# RELAYS.net
KiCad netlist of a schematic drawn in Altium Designer
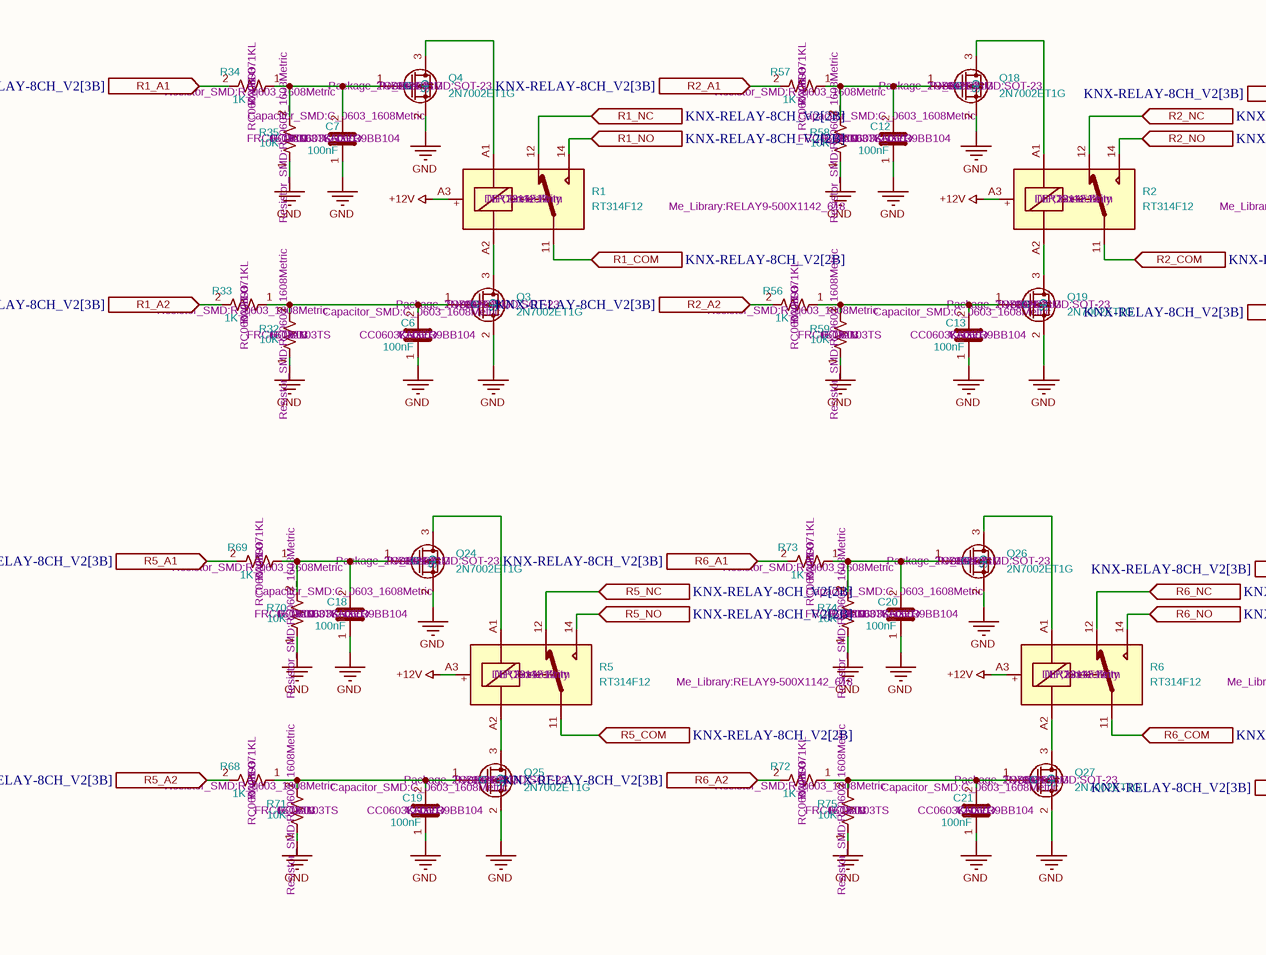
[diagram p0: RELAYS.SchDoc, left]
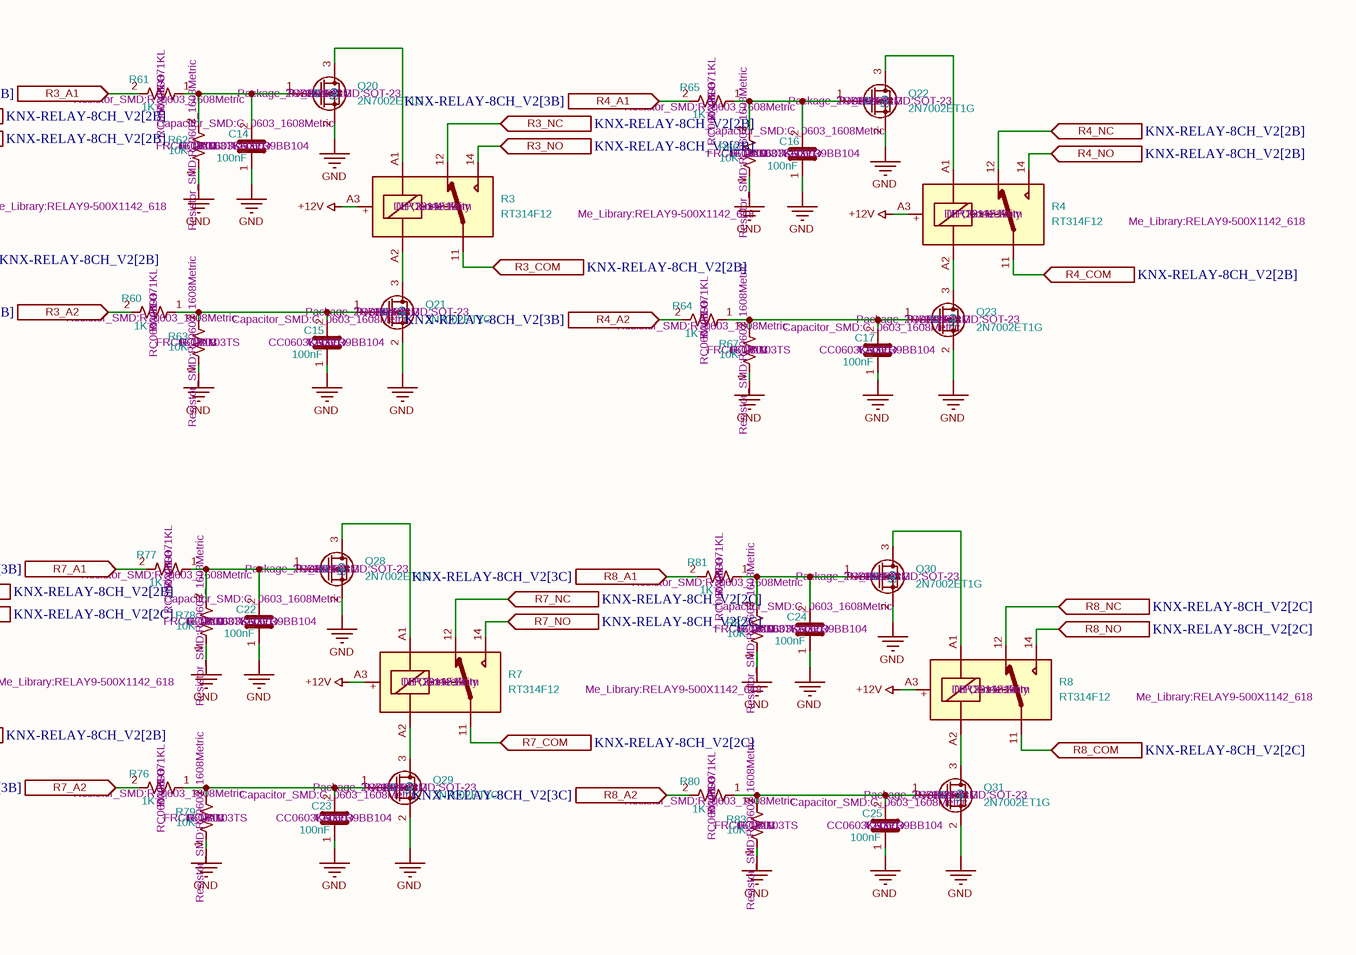
[diagram p1: RELAYS.SchDoc, right]

(export (version "E")
  (design (tool "Eeschema 10.0.6"))
  (components
    (comp (ref "C6")
      (value "100nF")
      (footprint "Capacitor_SMD:C_0603_1608Metric")
      (fields
        (field (name "MANUFACTURER PART NUMBER") "CC0603KRX7R9BB104")
        (field (name "MANUFACTURER") "YAGEO")
        (field (name "PACKAGE") "C_0603")
      )
      (libsource (lib "*") (part "C_3"))
    )
    (comp (ref "C7")
      (value "100nF")
      (footprint "Capacitor_SMD:C_0603_1608Metric")
      (fields
        (field (name "MANUFACTURER PART NUMBER") "CC0603KRX7R9BB104")
        (field (name "MANUFACTURER") "YAGEO")
        (field (name "PACKAGE") "C_0603")
      )
      (libsource (lib "*") (part "C_3"))
    )
    (comp (ref "C12")
      (value "100nF")
      (footprint "Capacitor_SMD:C_0603_1608Metric")
      (fields
        (field (name "MANUFACTURER PART NUMBER") "CC0603KRX7R9BB104")
        (field (name "MANUFACTURER") "YAGEO")
        (field (name "PACKAGE") "C_0603")
      )
      (libsource (lib "*") (part "C_3"))
    )
    (comp (ref "C13")
      (value "100nF")
      (footprint "Capacitor_SMD:C_0603_1608Metric")
      (fields
        (field (name "MANUFACTURER PART NUMBER") "CC0603KRX7R9BB104")
        (field (name "MANUFACTURER") "YAGEO")
        (field (name "PACKAGE") "C_0603")
      )
      (libsource (lib "*") (part "C_3"))
    )
    (comp (ref "C14")
      (value "100nF")
      (footprint "Capacitor_SMD:C_0603_1608Metric")
      (fields
        (field (name "MANUFACTURER PART NUMBER") "CC0603KRX7R9BB104")
        (field (name "MANUFACTURER") "YAGEO")
        (field (name "PACKAGE") "C_0603")
      )
      (libsource (lib "*") (part "C_3"))
    )
    (comp (ref "C15")
      (value "100nF")
      (footprint "Capacitor_SMD:C_0603_1608Metric")
      (fields
        (field (name "MANUFACTURER PART NUMBER") "CC0603KRX7R9BB104")
        (field (name "MANUFACTURER") "YAGEO")
        (field (name "PACKAGE") "C_0603")
      )
      (libsource (lib "*") (part "C_3"))
    )
    (comp (ref "C16")
      (value "100nF")
      (footprint "Capacitor_SMD:C_0603_1608Metric")
      (fields
        (field (name "MANUFACTURER PART NUMBER") "CC0603KRX7R9BB104")
        (field (name "MANUFACTURER") "YAGEO")
        (field (name "PACKAGE") "C_0603")
      )
      (libsource (lib "*") (part "C_3"))
    )
    (comp (ref "C17")
      (value "100nF")
      (footprint "Capacitor_SMD:C_0603_1608Metric")
      (fields
        (field (name "MANUFACTURER PART NUMBER") "CC0603KRX7R9BB104")
        (field (name "MANUFACTURER") "YAGEO")
        (field (name "PACKAGE") "C_0603")
      )
      (libsource (lib "*") (part "C_3"))
    )
    (comp (ref "C18")
      (value "100nF")
      (footprint "Capacitor_SMD:C_0603_1608Metric")
      (fields
        (field (name "MANUFACTURER PART NUMBER") "CC0603KRX7R9BB104")
        (field (name "MANUFACTURER") "YAGEO")
        (field (name "PACKAGE") "C_0603")
      )
      (libsource (lib "*") (part "C_3"))
    )
    (comp (ref "C19")
      (value "100nF")
      (footprint "Capacitor_SMD:C_0603_1608Metric")
      (fields
        (field (name "MANUFACTURER PART NUMBER") "CC0603KRX7R9BB104")
        (field (name "MANUFACTURER") "YAGEO")
        (field (name "PACKAGE") "C_0603")
      )
      (libsource (lib "*") (part "C_3"))
    )
    (comp (ref "C20")
      (value "100nF")
      (footprint "Capacitor_SMD:C_0603_1608Metric")
      (fields
        (field (name "MANUFACTURER PART NUMBER") "CC0603KRX7R9BB104")
        (field (name "MANUFACTURER") "YAGEO")
        (field (name "PACKAGE") "C_0603")
      )
      (libsource (lib "*") (part "C_3"))
    )
    (comp (ref "C21")
      (value "100nF")
      (footprint "Capacitor_SMD:C_0603_1608Metric")
      (fields
        (field (name "MANUFACTURER PART NUMBER") "CC0603KRX7R9BB104")
        (field (name "MANUFACTURER") "YAGEO")
        (field (name "PACKAGE") "C_0603")
      )
      (libsource (lib "*") (part "C_3"))
    )
    (comp (ref "C22")
      (value "100nF")
      (footprint "Capacitor_SMD:C_0603_1608Metric")
      (fields
        (field (name "MANUFACTURER PART NUMBER") "CC0603KRX7R9BB104")
        (field (name "MANUFACTURER") "YAGEO")
        (field (name "PACKAGE") "C_0603")
      )
      (libsource (lib "*") (part "C_3"))
    )
    (comp (ref "C23")
      (value "100nF")
      (footprint "Capacitor_SMD:C_0603_1608Metric")
      (fields
        (field (name "MANUFACTURER PART NUMBER") "CC0603KRX7R9BB104")
        (field (name "MANUFACTURER") "YAGEO")
        (field (name "PACKAGE") "C_0603")
      )
      (libsource (lib "*") (part "C_3"))
    )
    (comp (ref "C24")
      (value "100nF")
      (footprint "Capacitor_SMD:C_0603_1608Metric")
      (fields
        (field (name "MANUFACTURER PART NUMBER") "CC0603KRX7R9BB104")
        (field (name "MANUFACTURER") "YAGEO")
        (field (name "PACKAGE") "C_0603")
      )
      (libsource (lib "*") (part "C_3"))
    )
    (comp (ref "C25")
      (value "100nF")
      (footprint "Capacitor_SMD:C_0603_1608Metric")
      (fields
        (field (name "MANUFACTURER PART NUMBER") "CC0603KRX7R9BB104")
        (field (name "MANUFACTURER") "YAGEO")
        (field (name "PACKAGE") "C_0603")
      )
      (libsource (lib "*") (part "C_3"))
    )
    (comp (ref "Q3")
      (value "2N7002ET1G")
      (footprint "Package_TO_SOT_SMD:SOT-23")
      (fields
        (field (name "MANUFACTURER PART NUMBER") "2N7002ET1G")
        (field (name "MANUFACTURER") "onsemi")
        (field (name "PACKAGE") "SOT-23")
      )
      (libsource (lib "Transistor_FET_Other") (part "Q_NMOS_Depletion_GSD"))
    )
    (comp (ref "Q4")
      (value "2N7002ET1G")
      (footprint "Package_TO_SOT_SMD:SOT-23")
      (fields
        (field (name "MANUFACTURER PART NUMBER") "2N7002ET1G")
        (field (name "MANUFACTURER") "onsemi")
        (field (name "PACKAGE") "SOT-23")
      )
      (libsource (lib "Transistor_FET_Other") (part "Q_NMOS_Depletion_GSD"))
    )
    (comp (ref "Q18")
      (value "2N7002ET1G")
      (footprint "Package_TO_SOT_SMD:SOT-23")
      (fields
        (field (name "MANUFACTURER PART NUMBER") "2N7002ET1G")
        (field (name "MANUFACTURER") "onsemi")
        (field (name "PACKAGE") "SOT-23")
      )
      (libsource (lib "Transistor_FET_Other") (part "Q_NMOS_Depletion_GSD"))
    )
    (comp (ref "Q19")
      (value "2N7002ET1G")
      (footprint "Package_TO_SOT_SMD:SOT-23")
      (fields
        (field (name "MANUFACTURER PART NUMBER") "2N7002ET1G")
        (field (name "MANUFACTURER") "onsemi")
        (field (name "PACKAGE") "SOT-23")
      )
      (libsource (lib "Transistor_FET_Other") (part "Q_NMOS_Depletion_GSD"))
    )
    (comp (ref "Q20")
      (value "2N7002ET1G")
      (footprint "Package_TO_SOT_SMD:SOT-23")
      (fields
        (field (name "MANUFACTURER PART NUMBER") "2N7002ET1G")
        (field (name "MANUFACTURER") "onsemi")
        (field (name "PACKAGE") "SOT-23")
      )
      (libsource (lib "Transistor_FET_Other") (part "Q_NMOS_Depletion_GSD"))
    )
    (comp (ref "Q21")
      (value "2N7002ET1G")
      (footprint "Package_TO_SOT_SMD:SOT-23")
      (fields
        (field (name "MANUFACTURER PART NUMBER") "2N7002ET1G")
        (field (name "MANUFACTURER") "onsemi")
        (field (name "PACKAGE") "SOT-23")
      )
      (libsource (lib "Transistor_FET_Other") (part "Q_NMOS_Depletion_GSD"))
    )
    (comp (ref "Q22")
      (value "2N7002ET1G")
      (footprint "Package_TO_SOT_SMD:SOT-23")
      (fields
        (field (name "MANUFACTURER PART NUMBER") "2N7002ET1G")
        (field (name "MANUFACTURER") "onsemi")
        (field (name "PACKAGE") "SOT-23")
      )
      (libsource (lib "Transistor_FET_Other") (part "Q_NMOS_Depletion_GSD"))
    )
    (comp (ref "Q23")
      (value "2N7002ET1G")
      (footprint "Package_TO_SOT_SMD:SOT-23")
      (fields
        (field (name "MANUFACTURER PART NUMBER") "2N7002ET1G")
        (field (name "MANUFACTURER") "onsemi")
        (field (name "PACKAGE") "SOT-23")
      )
      (libsource (lib "Transistor_FET_Other") (part "Q_NMOS_Depletion_GSD"))
    )
    (comp (ref "Q24")
      (value "2N7002ET1G")
      (footprint "Package_TO_SOT_SMD:SOT-23")
      (fields
        (field (name "MANUFACTURER PART NUMBER") "2N7002ET1G")
        (field (name "MANUFACTURER") "onsemi")
        (field (name "PACKAGE") "SOT-23")
      )
      (libsource (lib "Transistor_FET_Other") (part "Q_NMOS_Depletion_GSD"))
    )
    (comp (ref "Q25")
      (value "2N7002ET1G")
      (footprint "Package_TO_SOT_SMD:SOT-23")
      (fields
        (field (name "MANUFACTURER PART NUMBER") "2N7002ET1G")
        (field (name "MANUFACTURER") "onsemi")
        (field (name "PACKAGE") "SOT-23")
      )
      (libsource (lib "Transistor_FET_Other") (part "Q_NMOS_Depletion_GSD"))
    )
    (comp (ref "Q26")
      (value "2N7002ET1G")
      (footprint "Package_TO_SOT_SMD:SOT-23")
      (fields
        (field (name "MANUFACTURER PART NUMBER") "2N7002ET1G")
        (field (name "MANUFACTURER") "onsemi")
        (field (name "PACKAGE") "SOT-23")
      )
      (libsource (lib "Transistor_FET_Other") (part "Q_NMOS_Depletion_GSD"))
    )
    (comp (ref "Q27")
      (value "2N7002ET1G")
      (footprint "Package_TO_SOT_SMD:SOT-23")
      (fields
        (field (name "MANUFACTURER PART NUMBER") "2N7002ET1G")
        (field (name "MANUFACTURER") "onsemi")
        (field (name "PACKAGE") "SOT-23")
      )
      (libsource (lib "Transistor_FET_Other") (part "Q_NMOS_Depletion_GSD"))
    )
    (comp (ref "Q28")
      (value "2N7002ET1G")
      (footprint "Package_TO_SOT_SMD:SOT-23")
      (fields
        (field (name "MANUFACTURER PART NUMBER") "2N7002ET1G")
        (field (name "MANUFACTURER") "onsemi")
        (field (name "PACKAGE") "SOT-23")
      )
      (libsource (lib "Transistor_FET_Other") (part "Q_NMOS_Depletion_GSD"))
    )
    (comp (ref "Q29")
      (value "2N7002ET1G")
      (footprint "Package_TO_SOT_SMD:SOT-23")
      (fields
        (field (name "MANUFACTURER PART NUMBER") "2N7002ET1G")
        (field (name "MANUFACTURER") "onsemi")
        (field (name "PACKAGE") "SOT-23")
      )
      (libsource (lib "Transistor_FET_Other") (part "Q_NMOS_Depletion_GSD"))
    )
    (comp (ref "Q30")
      (value "2N7002ET1G")
      (footprint "Package_TO_SOT_SMD:SOT-23")
      (fields
        (field (name "MANUFACTURER PART NUMBER") "2N7002ET1G")
        (field (name "MANUFACTURER") "onsemi")
        (field (name "PACKAGE") "SOT-23")
      )
      (libsource (lib "Transistor_FET_Other") (part "Q_NMOS_Depletion_GSD"))
    )
    (comp (ref "Q31")
      (value "2N7002ET1G")
      (footprint "Package_TO_SOT_SMD:SOT-23")
      (fields
        (field (name "MANUFACTURER PART NUMBER") "2N7002ET1G")
        (field (name "MANUFACTURER") "onsemi")
        (field (name "PACKAGE") "SOT-23")
      )
      (libsource (lib "Transistor_FET_Other") (part "Q_NMOS_Depletion_GSD"))
    )
    (comp (ref "R1")
      (value "RT314F12")
      (footprint "Me_Library:RELAY9-500X1142_618")
      (fields
        (field (name "MANUFACTURER PART NUMBER") "RT314F12")
        (field (name "MANUFACTURER") "TE Connectivity")
        (field (name "PACKAGE") "DIP,29x12.7mm")
      )
      (libsource (lib "Me_Library") (part "RT314A03"))
    )
    (comp (ref "R2")
      (value "RT314F12")
      (footprint "Me_Library:RELAY9-500X1142_618")
      (fields
        (field (name "MANUFACTURER PART NUMBER") "RT314F12")
        (field (name "MANUFACTURER") "TE Connectivity")
        (field (name "PACKAGE") "DIP,29x12.7mm")
      )
      (libsource (lib "Me_Library") (part "RT314A03"))
    )
    (comp (ref "R3")
      (value "RT314F12")
      (footprint "Me_Library:RELAY9-500X1142_618")
      (fields
        (field (name "MANUFACTURER PART NUMBER") "RT314F12")
        (field (name "MANUFACTURER") "TE Connectivity")
        (field (name "PACKAGE") "DIP,29x12.7mm")
      )
      (libsource (lib "Me_Library") (part "RT314A03"))
    )
    (comp (ref "R4")
      (value "RT314F12")
      (footprint "Me_Library:RELAY9-500X1142_618")
      (fields
        (field (name "MANUFACTURER PART NUMBER") "RT314F12")
        (field (name "MANUFACTURER") "TE Connectivity")
        (field (name "PACKAGE") "DIP,29x12.7mm")
      )
      (libsource (lib "Me_Library") (part "RT314A03"))
    )
    (comp (ref "R5")
      (value "RT314F12")
      (footprint "Me_Library:RELAY9-500X1142_618")
      (fields
        (field (name "MANUFACTURER PART NUMBER") "RT314F12")
        (field (name "MANUFACTURER") "TE Connectivity")
        (field (name "PACKAGE") "DIP,29x12.7mm")
      )
      (libsource (lib "Me_Library") (part "RT314A03"))
    )
    (comp (ref "R6")
      (value "RT314F12")
      (footprint "Me_Library:RELAY9-500X1142_618")
      (fields
        (field (name "MANUFACTURER PART NUMBER") "RT314F12")
        (field (name "MANUFACTURER") "TE Connectivity")
        (field (name "PACKAGE") "DIP,29x12.7mm")
      )
      (libsource (lib "Me_Library") (part "RT314A03"))
    )
    (comp (ref "R7")
      (value "RT314F12")
      (footprint "Me_Library:RELAY9-500X1142_618")
      (fields
        (field (name "MANUFACTURER PART NUMBER") "RT314F12")
        (field (name "MANUFACTURER") "TE Connectivity")
        (field (name "PACKAGE") "DIP,29x12.7mm")
      )
      (libsource (lib "Me_Library") (part "RT314A03"))
    )
    (comp (ref "R8")
      (value "RT314F12")
      (footprint "Me_Library:RELAY9-500X1142_618")
      (fields
        (field (name "MANUFACTURER PART NUMBER") "RT314F12")
        (field (name "MANUFACTURER") "TE Connectivity")
        (field (name "PACKAGE") "DIP,29x12.7mm")
      )
      (libsource (lib "Me_Library") (part "RT314A03"))
    )
    (comp (ref "R32")
      (value "10K")
      (footprint "Resistor_SMD:R_0603_1608Metric")
      (fields
        (field (name "MANUFACTURER PART NUMBER") "FRC0603J103TS")
        (field (name "MANUFACTURER") "FOJAN")
        (field (name "PACKAGE") "R_0603")
      )
      (libsource (lib "Device") (part "R_US"))
    )
    (comp (ref "R33")
      (value "1K")
      (footprint "Resistor_SMD:R_0603_1608Metric")
      (fields
        (field (name "MANUFACTURER PART NUMBER") "RC0603JR-071KL")
        (field (name "MANUFACTURER") "YAGEO")
        (field (name "PACKAGE") "R_0603")
      )
      (libsource (lib "Device") (part "R_US"))
    )
    (comp (ref "R34")
      (value "1K")
      (footprint "Resistor_SMD:R_0603_1608Metric")
      (fields
        (field (name "MANUFACTURER PART NUMBER") "RC0603JR-071KL")
        (field (name "MANUFACTURER") "YAGEO")
        (field (name "PACKAGE") "R_0603")
      )
      (libsource (lib "Device") (part "R_US"))
    )
    (comp (ref "R35")
      (value "10K")
      (footprint "Resistor_SMD:R_0603_1608Metric")
      (fields
        (field (name "MANUFACTURER PART NUMBER") "FRC0603J103TS")
        (field (name "MANUFACTURER") "FOJAN")
        (field (name "PACKAGE") "R_0603")
      )
      (libsource (lib "Device") (part "R_US"))
    )
    (comp (ref "R56")
      (value "1K")
      (footprint "Resistor_SMD:R_0603_1608Metric")
      (fields
        (field (name "MANUFACTURER PART NUMBER") "RC0603JR-071KL")
        (field (name "MANUFACTURER") "YAGEO")
        (field (name "PACKAGE") "R_0603")
      )
      (libsource (lib "Device") (part "R_US"))
    )
    (comp (ref "R57")
      (value "1K")
      (footprint "Resistor_SMD:R_0603_1608Metric")
      (fields
        (field (name "MANUFACTURER PART NUMBER") "RC0603JR-071KL")
        (field (name "MANUFACTURER") "YAGEO")
        (field (name "PACKAGE") "R_0603")
      )
      (libsource (lib "Device") (part "R_US"))
    )
    (comp (ref "R58")
      (value "10K")
      (footprint "Resistor_SMD:R_0603_1608Metric")
      (fields
        (field (name "MANUFACTURER PART NUMBER") "FRC0603J103TS")
        (field (name "MANUFACTURER") "FOJAN")
        (field (name "PACKAGE") "R_0603")
      )
      (libsource (lib "Device") (part "R_US"))
    )
    (comp (ref "R59")
      (value "10K")
      (footprint "Resistor_SMD:R_0603_1608Metric")
      (fields
        (field (name "MANUFACTURER PART NUMBER") "FRC0603J103TS")
        (field (name "MANUFACTURER") "FOJAN")
        (field (name "PACKAGE") "R_0603")
      )
      (libsource (lib "Device") (part "R_US"))
    )
    (comp (ref "R60")
      (value "1K")
      (footprint "Resistor_SMD:R_0603_1608Metric")
      (fields
        (field (name "MANUFACTURER PART NUMBER") "RC0603JR-071KL")
        (field (name "MANUFACTURER") "YAGEO")
        (field (name "PACKAGE") "R_0603")
      )
      (libsource (lib "Device") (part "R_US"))
    )
    (comp (ref "R61")
      (value "1K")
      (footprint "Resistor_SMD:R_0603_1608Metric")
      (fields
        (field (name "MANUFACTURER PART NUMBER") "RC0603JR-071KL")
        (field (name "MANUFACTURER") "YAGEO")
        (field (name "PACKAGE") "R_0603")
      )
      (libsource (lib "Device") (part "R_US"))
    )
    (comp (ref "R62")
      (value "10K")
      (footprint "Resistor_SMD:R_0603_1608Metric")
      (fields
        (field (name "MANUFACTURER PART NUMBER") "FRC0603J103TS")
        (field (name "MANUFACTURER") "FOJAN")
        (field (name "PACKAGE") "R_0603")
      )
      (libsource (lib "Device") (part "R_US"))
    )
    (comp (ref "R63")
      (value "10K")
      (footprint "Resistor_SMD:R_0603_1608Metric")
      (fields
        (field (name "MANUFACTURER PART NUMBER") "FRC0603J103TS")
        (field (name "MANUFACTURER") "FOJAN")
        (field (name "PACKAGE") "R_0603")
      )
      (libsource (lib "Device") (part "R_US"))
    )
    (comp (ref "R64")
      (value "1K")
      (footprint "Resistor_SMD:R_0603_1608Metric")
      (fields
        (field (name "MANUFACTURER PART NUMBER") "RC0603JR-071KL")
        (field (name "MANUFACTURER") "YAGEO")
        (field (name "PACKAGE") "R_0603")
      )
      (libsource (lib "Device") (part "R_US"))
    )
    (comp (ref "R65")
      (value "1K")
      (footprint "Resistor_SMD:R_0603_1608Metric")
      (fields
        (field (name "MANUFACTURER PART NUMBER") "RC0603JR-071KL")
        (field (name "MANUFACTURER") "YAGEO")
        (field (name "PACKAGE") "R_0603")
      )
      (libsource (lib "Device") (part "R_US"))
    )
    (comp (ref "R66")
      (value "10K")
      (footprint "Resistor_SMD:R_0603_1608Metric")
      (fields
        (field (name "MANUFACTURER PART NUMBER") "FRC0603J103TS")
        (field (name "MANUFACTURER") "FOJAN")
        (field (name "PACKAGE") "R_0603")
      )
      (libsource (lib "Device") (part "R_US"))
    )
    (comp (ref "R67")
      (value "10K")
      (footprint "Resistor_SMD:R_0603_1608Metric")
      (fields
        (field (name "MANUFACTURER PART NUMBER") "FRC0603J103TS")
        (field (name "MANUFACTURER") "FOJAN")
        (field (name "PACKAGE") "R_0603")
      )
      (libsource (lib "Device") (part "R_US"))
    )
    (comp (ref "R68")
      (value "1K")
      (footprint "Resistor_SMD:R_0603_1608Metric")
      (fields
        (field (name "MANUFACTURER PART NUMBER") "RC0603JR-071KL")
        (field (name "MANUFACTURER") "YAGEO")
        (field (name "PACKAGE") "R_0603")
      )
      (libsource (lib "Device") (part "R_US"))
    )
    (comp (ref "R69")
      (value "1K")
      (footprint "Resistor_SMD:R_0603_1608Metric")
      (fields
        (field (name "MANUFACTURER PART NUMBER") "RC0603JR-071KL")
        (field (name "MANUFACTURER") "YAGEO")
        (field (name "PACKAGE") "R_0603")
      )
      (libsource (lib "Device") (part "R_US"))
    )
    (comp (ref "R70")
      (value "10K")
      (footprint "Resistor_SMD:R_0603_1608Metric")
      (fields
        (field (name "MANUFACTURER PART NUMBER") "FRC0603J103TS")
        (field (name "MANUFACTURER") "FOJAN")
        (field (name "PACKAGE") "R_0603")
      )
      (libsource (lib "Device") (part "R_US"))
    )
    (comp (ref "R71")
      (value "10K")
      (footprint "Resistor_SMD:R_0603_1608Metric")
      (fields
        (field (name "MANUFACTURER PART NUMBER") "FRC0603J103TS")
        (field (name "MANUFACTURER") "FOJAN")
        (field (name "PACKAGE") "R_0603")
      )
      (libsource (lib "Device") (part "R_US"))
    )
    (comp (ref "R72")
      (value "1K")
      (footprint "Resistor_SMD:R_0603_1608Metric")
      (fields
        (field (name "MANUFACTURER PART NUMBER") "RC0603JR-071KL")
        (field (name "MANUFACTURER") "YAGEO")
        (field (name "PACKAGE") "R_0603")
      )
      (libsource (lib "Device") (part "R_US"))
    )
    (comp (ref "R73")
      (value "1K")
      (footprint "Resistor_SMD:R_0603_1608Metric")
      (fields
        (field (name "MANUFACTURER PART NUMBER") "RC0603JR-071KL")
        (field (name "MANUFACTURER") "YAGEO")
        (field (name "PACKAGE") "R_0603")
      )
      (libsource (lib "Device") (part "R_US"))
    )
    (comp (ref "R74")
      (value "10K")
      (footprint "Resistor_SMD:R_0603_1608Metric")
      (fields
        (field (name "MANUFACTURER PART NUMBER") "FRC0603J103TS")
        (field (name "MANUFACTURER") "FOJAN")
        (field (name "PACKAGE") "R_0603")
      )
      (libsource (lib "Device") (part "R_US"))
    )
    (comp (ref "R75")
      (value "10K")
      (footprint "Resistor_SMD:R_0603_1608Metric")
      (fields
        (field (name "MANUFACTURER PART NUMBER") "FRC0603J103TS")
        (field (name "MANUFACTURER") "FOJAN")
        (field (name "PACKAGE") "R_0603")
      )
      (libsource (lib "Device") (part "R_US"))
    )
    (comp (ref "R76")
      (value "1K")
      (footprint "Resistor_SMD:R_0603_1608Metric")
      (fields
        (field (name "MANUFACTURER PART NUMBER") "RC0603JR-071KL")
        (field (name "MANUFACTURER") "YAGEO")
        (field (name "PACKAGE") "R_0603")
      )
      (libsource (lib "Device") (part "R_US"))
    )
    (comp (ref "R77")
      (value "1K")
      (footprint "Resistor_SMD:R_0603_1608Metric")
      (fields
        (field (name "MANUFACTURER PART NUMBER") "RC0603JR-071KL")
        (field (name "MANUFACTURER") "YAGEO")
        (field (name "PACKAGE") "R_0603")
      )
      (libsource (lib "Device") (part "R_US"))
    )
    (comp (ref "R78")
      (value "10K")
      (footprint "Resistor_SMD:R_0603_1608Metric")
      (fields
        (field (name "MANUFACTURER PART NUMBER") "FRC0603J103TS")
        (field (name "MANUFACTURER") "FOJAN")
        (field (name "PACKAGE") "R_0603")
      )
      (libsource (lib "Device") (part "R_US"))
    )
    (comp (ref "R79")
      (value "10K")
      (footprint "Resistor_SMD:R_0603_1608Metric")
      (fields
        (field (name "MANUFACTURER PART NUMBER") "FRC0603J103TS")
        (field (name "MANUFACTURER") "FOJAN")
        (field (name "PACKAGE") "R_0603")
      )
      (libsource (lib "Device") (part "R_US"))
    )
    (comp (ref "R80")
      (value "1K")
      (footprint "Resistor_SMD:R_0603_1608Metric")
      (fields
        (field (name "MANUFACTURER PART NUMBER") "RC0603JR-071KL")
        (field (name "MANUFACTURER") "YAGEO")
        (field (name "PACKAGE") "R_0603")
      )
      (libsource (lib "Device") (part "R_US"))
    )
    (comp (ref "R81")
      (value "1K")
      (footprint "Resistor_SMD:R_0603_1608Metric")
      (fields
        (field (name "MANUFACTURER PART NUMBER") "RC0603JR-071KL")
        (field (name "MANUFACTURER") "YAGEO")
        (field (name "PACKAGE") "R_0603")
      )
      (libsource (lib "Device") (part "R_US"))
    )
    (comp (ref "R82")
      (value "10K")
      (footprint "Resistor_SMD:R_0603_1608Metric")
      (fields
        (field (name "MANUFACTURER PART NUMBER") "FRC0603J103TS")
        (field (name "MANUFACTURER") "FOJAN")
        (field (name "PACKAGE") "R_0603")
      )
      (libsource (lib "Device") (part "R_US"))
    )
    (comp (ref "R83")
      (value "10K")
      (footprint "Resistor_SMD:R_0603_1608Metric")
      (fields
        (field (name "MANUFACTURER PART NUMBER") "FRC0603J103TS")
        (field (name "MANUFACTURER") "FOJAN")
        (field (name "PACKAGE") "R_0603")
      )
      (libsource (lib "Device") (part "R_US"))
    )
  )
  (nets
    (net (code "1") (name "+12V") (class "Default")
      (node (ref "R1") (pin "A3") (pinfunction "A3_A3") (pintype "passive"))
      (node (ref "R2") (pin "A3") (pinfunction "A3_A3") (pintype "passive"))
      (node (ref "R3") (pin "A3") (pinfunction "A3_A3") (pintype "passive"))
      (node (ref "R4") (pin "A3") (pinfunction "A3_A3") (pintype "passive"))
      (node (ref "R5") (pin "A3") (pinfunction "A3_A3") (pintype "passive"))
      (node (ref "R6") (pin "A3") (pinfunction "A3_A3") (pintype "passive"))
      (node (ref "R7") (pin "A3") (pinfunction "A3_A3") (pintype "passive"))
      (node (ref "R8") (pin "A3") (pinfunction "A3_A3") (pintype "passive"))
    )
    (net (code "2") (name "/R1_A1") (class "Default")
      (node (ref "R34") (pin "2") (pinfunction "2_2") (pintype "passive"))
    )
    (net (code "3") (name "/R1_A2") (class "Default")
      (node (ref "R33") (pin "2") (pinfunction "2_2") (pintype "passive"))
    )
    (net (code "4") (name "/R1_COM") (class "Default")
      (node (ref "R1") (pin "11") (pinfunction "11_11") (pintype "passive"))
    )
    (net (code "5") (name "/R1_NC") (class "Default")
      (node (ref "R1") (pin "12") (pinfunction "12_12") (pintype "passive"))
    )
    (net (code "6") (name "/R1_NO") (class "Default")
      (node (ref "R1") (pin "14") (pinfunction "14_14") (pintype "passive"))
    )
    (net (code "7") (name "/R2_A1") (class "Default")
      (node (ref "R57") (pin "2") (pinfunction "2_2") (pintype "passive"))
    )
    (net (code "8") (name "/R2_A2") (class "Default")
      (node (ref "R56") (pin "2") (pinfunction "2_2") (pintype "passive"))
    )
    (net (code "9") (name "/R2_COM") (class "Default")
      (node (ref "R2") (pin "11") (pinfunction "11_11") (pintype "passive"))
    )
    (net (code "10") (name "/R2_NC") (class "Default")
      (node (ref "R2") (pin "12") (pinfunction "12_12") (pintype "passive"))
    )
    (net (code "11") (name "/R2_NO") (class "Default")
      (node (ref "R2") (pin "14") (pinfunction "14_14") (pintype "passive"))
    )
    (net (code "12") (name "/R3_A1") (class "Default")
      (node (ref "R61") (pin "2") (pinfunction "2_2") (pintype "passive"))
    )
    (net (code "13") (name "/R3_A2") (class "Default")
      (node (ref "R60") (pin "2") (pinfunction "2_2") (pintype "passive"))
    )
    (net (code "14") (name "/R3_COM") (class "Default")
      (node (ref "R3") (pin "11") (pinfunction "11_11") (pintype "passive"))
    )
    (net (code "15") (name "/R3_NC") (class "Default")
      (node (ref "R3") (pin "12") (pinfunction "12_12") (pintype "passive"))
    )
    (net (code "16") (name "/R3_NO") (class "Default")
      (node (ref "R3") (pin "14") (pinfunction "14_14") (pintype "passive"))
    )
    (net (code "17") (name "/R4_A1") (class "Default")
      (node (ref "R65") (pin "2") (pinfunction "2_2") (pintype "passive"))
    )
    (net (code "18") (name "/R4_A2") (class "Default")
      (node (ref "R64") (pin "2") (pinfunction "2_2") (pintype "passive"))
    )
    (net (code "19") (name "/R4_COM") (class "Default")
      (node (ref "R4") (pin "11") (pinfunction "11_11") (pintype "passive"))
    )
    (net (code "20") (name "/R4_NC") (class "Default")
      (node (ref "R4") (pin "12") (pinfunction "12_12") (pintype "passive"))
    )
    (net (code "21") (name "/R4_NO") (class "Default")
      (node (ref "R4") (pin "14") (pinfunction "14_14") (pintype "passive"))
    )
    (net (code "22") (name "/R5_A1") (class "Default")
      (node (ref "R69") (pin "2") (pinfunction "2_2") (pintype "passive"))
    )
    (net (code "23") (name "/R5_A2") (class "Default")
      (node (ref "R68") (pin "2") (pinfunction "2_2") (pintype "passive"))
    )
    (net (code "24") (name "/R5_COM") (class "Default")
      (node (ref "R5") (pin "11") (pinfunction "11_11") (pintype "passive"))
    )
    (net (code "25") (name "/R5_NC") (class "Default")
      (node (ref "R5") (pin "12") (pinfunction "12_12") (pintype "passive"))
    )
    (net (code "26") (name "/R5_NO") (class "Default")
      (node (ref "R5") (pin "14") (pinfunction "14_14") (pintype "passive"))
    )
    (net (code "27") (name "/R6_A1") (class "Default")
      (node (ref "R73") (pin "2") (pinfunction "2_2") (pintype "passive"))
    )
    (net (code "28") (name "/R6_A2") (class "Default")
      (node (ref "R72") (pin "2") (pinfunction "2_2") (pintype "passive"))
    )
    (net (code "29") (name "/R6_COM") (class "Default")
      (node (ref "R6") (pin "11") (pinfunction "11_11") (pintype "passive"))
    )
    (net (code "30") (name "/R6_NC") (class "Default")
      (node (ref "R6") (pin "12") (pinfunction "12_12") (pintype "passive"))
    )
    (net (code "31") (name "/R6_NO") (class "Default")
      (node (ref "R6") (pin "14") (pinfunction "14_14") (pintype "passive"))
    )
    (net (code "32") (name "/R7_A1") (class "Default")
      (node (ref "R77") (pin "2") (pinfunction "2_2") (pintype "passive"))
    )
    (net (code "33") (name "/R7_A2") (class "Default")
      (node (ref "R76") (pin "2") (pinfunction "2_2") (pintype "passive"))
    )
    (net (code "34") (name "/R7_COM") (class "Default")
      (node (ref "R7") (pin "11") (pinfunction "11_11") (pintype "passive"))
    )
    (net (code "35") (name "/R7_NC") (class "Default")
      (node (ref "R7") (pin "12") (pinfunction "12_12") (pintype "passive"))
    )
    (net (code "36") (name "/R7_NO") (class "Default")
      (node (ref "R7") (pin "14") (pinfunction "14_14") (pintype "passive"))
    )
    (net (code "37") (name "/R8_A1") (class "Default")
      (node (ref "R81") (pin "2") (pinfunction "2_2") (pintype "passive"))
    )
    (net (code "38") (name "/R8_A2") (class "Default")
      (node (ref "R80") (pin "2") (pinfunction "2_2") (pintype "passive"))
    )
    (net (code "39") (name "/R8_COM") (class "Default")
      (node (ref "R8") (pin "11") (pinfunction "11_11") (pintype "passive"))
    )
    (net (code "40") (name "/R8_NC") (class "Default")
      (node (ref "R8") (pin "12") (pinfunction "12_12") (pintype "passive"))
    )
    (net (code "41") (name "/R8_NO") (class "Default")
      (node (ref "R8") (pin "14") (pinfunction "14_14") (pintype "passive"))
    )
    (net (code "42") (name "GND") (class "Default")
      (node (ref "C12") (pin "1") (pinfunction "1_1") (pintype "passive"))
      (node (ref "C13") (pin "1") (pinfunction "1_1") (pintype "passive"))
      (node (ref "C14") (pin "1") (pinfunction "1_1") (pintype "passive"))
      (node (ref "C15") (pin "1") (pinfunction "1_1") (pintype "passive"))
      (node (ref "C16") (pin "1") (pinfunction "1_1") (pintype "passive"))
      (node (ref "C17") (pin "1") (pinfunction "1_1") (pintype "passive"))
      (node (ref "C18") (pin "1") (pinfunction "1_1") (pintype "passive"))
      (node (ref "C19") (pin "1") (pinfunction "1_1") (pintype "passive"))
      (node (ref "C20") (pin "1") (pinfunction "1_1") (pintype "passive"))
      (node (ref "C21") (pin "1") (pinfunction "1_1") (pintype "passive"))
      (node (ref "C22") (pin "1") (pinfunction "1_1") (pintype "passive"))
      (node (ref "C23") (pin "1") (pinfunction "1_1") (pintype "passive"))
      (node (ref "C24") (pin "1") (pinfunction "1_1") (pintype "passive"))
      (node (ref "C25") (pin "1") (pinfunction "1_1") (pintype "passive"))
      (node (ref "C6") (pin "1") (pinfunction "1_1") (pintype "passive"))
      (node (ref "C7") (pin "1") (pinfunction "1_1") (pintype "passive"))
      (node (ref "Q18") (pin "2") (pinfunction "S_2") (pintype "passive"))
      (node (ref "Q19") (pin "2") (pinfunction "S_2") (pintype "passive"))
      (node (ref "Q20") (pin "2") (pinfunction "S_2") (pintype "passive"))
      (node (ref "Q21") (pin "2") (pinfunction "S_2") (pintype "passive"))
      (node (ref "Q22") (pin "2") (pinfunction "S_2") (pintype "passive"))
      (node (ref "Q23") (pin "2") (pinfunction "S_2") (pintype "passive"))
      (node (ref "Q24") (pin "2") (pinfunction "S_2") (pintype "passive"))
      (node (ref "Q25") (pin "2") (pinfunction "S_2") (pintype "passive"))
      (node (ref "Q26") (pin "2") (pinfunction "S_2") (pintype "passive"))
      (node (ref "Q27") (pin "2") (pinfunction "S_2") (pintype "passive"))
      (node (ref "Q28") (pin "2") (pinfunction "S_2") (pintype "passive"))
      (node (ref "Q29") (pin "2") (pinfunction "S_2") (pintype "passive"))
      (node (ref "Q3") (pin "2") (pinfunction "S_2") (pintype "passive"))
      (node (ref "Q30") (pin "2") (pinfunction "S_2") (pintype "passive"))
      (node (ref "Q31") (pin "2") (pinfunction "S_2") (pintype "passive"))
      (node (ref "Q4") (pin "2") (pinfunction "S_2") (pintype "passive"))
      (node (ref "R32") (pin "1") (pinfunction "1_1") (pintype "passive"))
      (node (ref "R35") (pin "1") (pinfunction "1_1") (pintype "passive"))
      (node (ref "R58") (pin "1") (pinfunction "1_1") (pintype "passive"))
      (node (ref "R59") (pin "1") (pinfunction "1_1") (pintype "passive"))
      (node (ref "R62") (pin "1") (pinfunction "1_1") (pintype "passive"))
      (node (ref "R63") (pin "1") (pinfunction "1_1") (pintype "passive"))
      (node (ref "R66") (pin "1") (pinfunction "1_1") (pintype "passive"))
      (node (ref "R67") (pin "1") (pinfunction "1_1") (pintype "passive"))
      (node (ref "R70") (pin "1") (pinfunction "1_1") (pintype "passive"))
      (node (ref "R71") (pin "1") (pinfunction "1_1") (pintype "passive"))
      (node (ref "R74") (pin "1") (pinfunction "1_1") (pintype "passive"))
      (node (ref "R75") (pin "1") (pinfunction "1_1") (pintype "passive"))
      (node (ref "R78") (pin "1") (pinfunction "1_1") (pintype "passive"))
      (node (ref "R79") (pin "1") (pinfunction "1_1") (pintype "passive"))
      (node (ref "R82") (pin "1") (pinfunction "1_1") (pintype "passive"))
      (node (ref "R83") (pin "1") (pinfunction "1_1") (pintype "passive"))
    )
    (net (code "43") (name "Net-(Q3-D)") (class "Default")
      (node (ref "Q3") (pin "3") (pinfunction "D_3") (pintype "passive"))
      (node (ref "R1") (pin "A2") (pinfunction "A2_A2") (pintype "passive"))
    )
    (net (code "44") (name "Net-(Q3-G)") (class "Default")
      (node (ref "C6") (pin "2") (pinfunction "2_2") (pintype "passive"))
      (node (ref "Q3") (pin "1") (pinfunction "G_1") (pintype "passive"))
      (node (ref "R32") (pin "2") (pinfunction "2_2") (pintype "passive"))
      (node (ref "R33") (pin "1") (pinfunction "1_1") (pintype "passive"))
    )
    (net (code "45") (name "Net-(Q4-D)") (class "Default")
      (node (ref "Q4") (pin "3") (pinfunction "D_3") (pintype "passive"))
      (node (ref "R1") (pin "A1") (pinfunction "A1_A1") (pintype "passive"))
    )
    (net (code "46") (name "Net-(Q4-G)") (class "Default")
      (node (ref "C7") (pin "2") (pinfunction "2_2") (pintype "passive"))
      (node (ref "Q4") (pin "1") (pinfunction "G_1") (pintype "passive"))
      (node (ref "R34") (pin "1") (pinfunction "1_1") (pintype "passive"))
      (node (ref "R35") (pin "2") (pinfunction "2_2") (pintype "passive"))
    )
    (net (code "47") (name "Net-(Q18-D)") (class "Default")
      (node (ref "Q18") (pin "3") (pinfunction "D_3") (pintype "passive"))
      (node (ref "R2") (pin "A1") (pinfunction "A1_A1") (pintype "passive"))
    )
    (net (code "48") (name "Net-(Q18-G)") (class "Default")
      (node (ref "C12") (pin "2") (pinfunction "2_2") (pintype "passive"))
      (node (ref "Q18") (pin "1") (pinfunction "G_1") (pintype "passive"))
      (node (ref "R57") (pin "1") (pinfunction "1_1") (pintype "passive"))
      (node (ref "R58") (pin "2") (pinfunction "2_2") (pintype "passive"))
    )
    (net (code "49") (name "Net-(Q19-D)") (class "Default")
      (node (ref "Q19") (pin "3") (pinfunction "D_3") (pintype "passive"))
      (node (ref "R2") (pin "A2") (pinfunction "A2_A2") (pintype "passive"))
    )
    (net (code "50") (name "Net-(Q19-G)") (class "Default")
      (node (ref "C13") (pin "2") (pinfunction "2_2") (pintype "passive"))
      (node (ref "Q19") (pin "1") (pinfunction "G_1") (pintype "passive"))
      (node (ref "R56") (pin "1") (pinfunction "1_1") (pintype "passive"))
      (node (ref "R59") (pin "2") (pinfunction "2_2") (pintype "passive"))
    )
    (net (code "51") (name "Net-(Q20-D)") (class "Default")
      (node (ref "Q20") (pin "3") (pinfunction "D_3") (pintype "passive"))
      (node (ref "R3") (pin "A1") (pinfunction "A1_A1") (pintype "passive"))
    )
    (net (code "52") (name "Net-(Q20-G)") (class "Default")
      (node (ref "C14") (pin "2") (pinfunction "2_2") (pintype "passive"))
      (node (ref "Q20") (pin "1") (pinfunction "G_1") (pintype "passive"))
      (node (ref "R61") (pin "1") (pinfunction "1_1") (pintype "passive"))
      (node (ref "R62") (pin "2") (pinfunction "2_2") (pintype "passive"))
    )
    (net (code "53") (name "Net-(Q21-D)") (class "Default")
      (node (ref "Q21") (pin "3") (pinfunction "D_3") (pintype "passive"))
      (node (ref "R3") (pin "A2") (pinfunction "A2_A2") (pintype "passive"))
    )
    (net (code "54") (name "Net-(Q21-G)") (class "Default")
      (node (ref "C15") (pin "2") (pinfunction "2_2") (pintype "passive"))
      (node (ref "Q21") (pin "1") (pinfunction "G_1") (pintype "passive"))
      (node (ref "R60") (pin "1") (pinfunction "1_1") (pintype "passive"))
      (node (ref "R63") (pin "2") (pinfunction "2_2") (pintype "passive"))
    )
    (net (code "55") (name "Net-(Q22-D)") (class "Default")
      (node (ref "Q22") (pin "3") (pinfunction "D_3") (pintype "passive"))
      (node (ref "R4") (pin "A1") (pinfunction "A1_A1") (pintype "passive"))
    )
    (net (code "56") (name "Net-(Q22-G)") (class "Default")
      (node (ref "C16") (pin "2") (pinfunction "2_2") (pintype "passive"))
      (node (ref "Q22") (pin "1") (pinfunction "G_1") (pintype "passive"))
      (node (ref "R65") (pin "1") (pinfunction "1_1") (pintype "passive"))
      (node (ref "R66") (pin "2") (pinfunction "2_2") (pintype "passive"))
    )
    (net (code "57") (name "Net-(Q23-D)") (class "Default")
      (node (ref "Q23") (pin "3") (pinfunction "D_3") (pintype "passive"))
      (node (ref "R4") (pin "A2") (pinfunction "A2_A2") (pintype "passive"))
    )
    (net (code "58") (name "Net-(Q23-G)") (class "Default")
      (node (ref "C17") (pin "2") (pinfunction "2_2") (pintype "passive"))
      (node (ref "Q23") (pin "1") (pinfunction "G_1") (pintype "passive"))
      (node (ref "R64") (pin "1") (pinfunction "1_1") (pintype "passive"))
      (node (ref "R67") (pin "2") (pinfunction "2_2") (pintype "passive"))
    )
    (net (code "59") (name "Net-(Q24-D)") (class "Default")
      (node (ref "Q24") (pin "3") (pinfunction "D_3") (pintype "passive"))
      (node (ref "R5") (pin "A1") (pinfunction "A1_A1") (pintype "passive"))
    )
    (net (code "60") (name "Net-(Q24-G)") (class "Default")
      (node (ref "C18") (pin "2") (pinfunction "2_2") (pintype "passive"))
      (node (ref "Q24") (pin "1") (pinfunction "G_1") (pintype "passive"))
      (node (ref "R69") (pin "1") (pinfunction "1_1") (pintype "passive"))
      (node (ref "R70") (pin "2") (pinfunction "2_2") (pintype "passive"))
    )
    (net (code "61") (name "Net-(Q25-D)") (class "Default")
      (node (ref "Q25") (pin "3") (pinfunction "D_3") (pintype "passive"))
      (node (ref "R5") (pin "A2") (pinfunction "A2_A2") (pintype "passive"))
    )
    (net (code "62") (name "Net-(Q25-G)") (class "Default")
      (node (ref "C19") (pin "2") (pinfunction "2_2") (pintype "passive"))
      (node (ref "Q25") (pin "1") (pinfunction "G_1") (pintype "passive"))
      (node (ref "R68") (pin "1") (pinfunction "1_1") (pintype "passive"))
      (node (ref "R71") (pin "2") (pinfunction "2_2") (pintype "passive"))
    )
    (net (code "63") (name "Net-(Q26-D)") (class "Default")
      (node (ref "Q26") (pin "3") (pinfunction "D_3") (pintype "passive"))
      (node (ref "R6") (pin "A1") (pinfunction "A1_A1") (pintype "passive"))
    )
    (net (code "64") (name "Net-(Q26-G)") (class "Default")
      (node (ref "C20") (pin "2") (pinfunction "2_2") (pintype "passive"))
      (node (ref "Q26") (pin "1") (pinfunction "G_1") (pintype "passive"))
      (node (ref "R73") (pin "1") (pinfunction "1_1") (pintype "passive"))
      (node (ref "R74") (pin "2") (pinfunction "2_2") (pintype "passive"))
    )
    (net (code "65") (name "Net-(Q27-D)") (class "Default")
      (node (ref "Q27") (pin "3") (pinfunction "D_3") (pintype "passive"))
      (node (ref "R6") (pin "A2") (pinfunction "A2_A2") (pintype "passive"))
    )
    (net (code "66") (name "Net-(Q27-G)") (class "Default")
      (node (ref "C21") (pin "2") (pinfunction "2_2") (pintype "passive"))
      (node (ref "Q27") (pin "1") (pinfunction "G_1") (pintype "passive"))
      (node (ref "R72") (pin "1") (pinfunction "1_1") (pintype "passive"))
      (node (ref "R75") (pin "2") (pinfunction "2_2") (pintype "passive"))
    )
    (net (code "67") (name "Net-(Q28-D)") (class "Default")
      (node (ref "Q28") (pin "3") (pinfunction "D_3") (pintype "passive"))
      (node (ref "R7") (pin "A1") (pinfunction "A1_A1") (pintype "passive"))
    )
    (net (code "68") (name "Net-(Q28-G)") (class "Default")
      (node (ref "C22") (pin "2") (pinfunction "2_2") (pintype "passive"))
      (node (ref "Q28") (pin "1") (pinfunction "G_1") (pintype "passive"))
      (node (ref "R77") (pin "1") (pinfunction "1_1") (pintype "passive"))
      (node (ref "R78") (pin "2") (pinfunction "2_2") (pintype "passive"))
    )
    (net (code "69") (name "Net-(Q29-D)") (class "Default")
      (node (ref "Q29") (pin "3") (pinfunction "D_3") (pintype "passive"))
      (node (ref "R7") (pin "A2") (pinfunction "A2_A2") (pintype "passive"))
    )
    (net (code "70") (name "Net-(Q29-G)") (class "Default")
      (node (ref "C23") (pin "2") (pinfunction "2_2") (pintype "passive"))
      (node (ref "Q29") (pin "1") (pinfunction "G_1") (pintype "passive"))
      (node (ref "R76") (pin "1") (pinfunction "1_1") (pintype "passive"))
      (node (ref "R79") (pin "2") (pinfunction "2_2") (pintype "passive"))
    )
    (net (code "71") (name "Net-(Q30-D)") (class "Default")
      (node (ref "Q30") (pin "3") (pinfunction "D_3") (pintype "passive"))
      (node (ref "R8") (pin "A1") (pinfunction "A1_A1") (pintype "passive"))
    )
    (net (code "72") (name "Net-(Q30-G)") (class "Default")
      (node (ref "C24") (pin "2") (pinfunction "2_2") (pintype "passive"))
      (node (ref "Q30") (pin "1") (pinfunction "G_1") (pintype "passive"))
      (node (ref "R81") (pin "1") (pinfunction "1_1") (pintype "passive"))
      (node (ref "R82") (pin "2") (pinfunction "2_2") (pintype "passive"))
    )
    (net (code "73") (name "Net-(Q31-D)") (class "Default")
      (node (ref "Q31") (pin "3") (pinfunction "D_3") (pintype "passive"))
      (node (ref "R8") (pin "A2") (pinfunction "A2_A2") (pintype "passive"))
    )
    (net (code "74") (name "Net-(Q31-G)") (class "Default")
      (node (ref "C25") (pin "2") (pinfunction "2_2") (pintype "passive"))
      (node (ref "Q31") (pin "1") (pinfunction "G_1") (pintype "passive"))
      (node (ref "R80") (pin "1") (pinfunction "1_1") (pintype "passive"))
      (node (ref "R83") (pin "2") (pinfunction "2_2") (pintype "passive"))
    )
  )
)
